# rev-tank-preamp.net
KiCad netlist of a schematic drawn in EAGLE
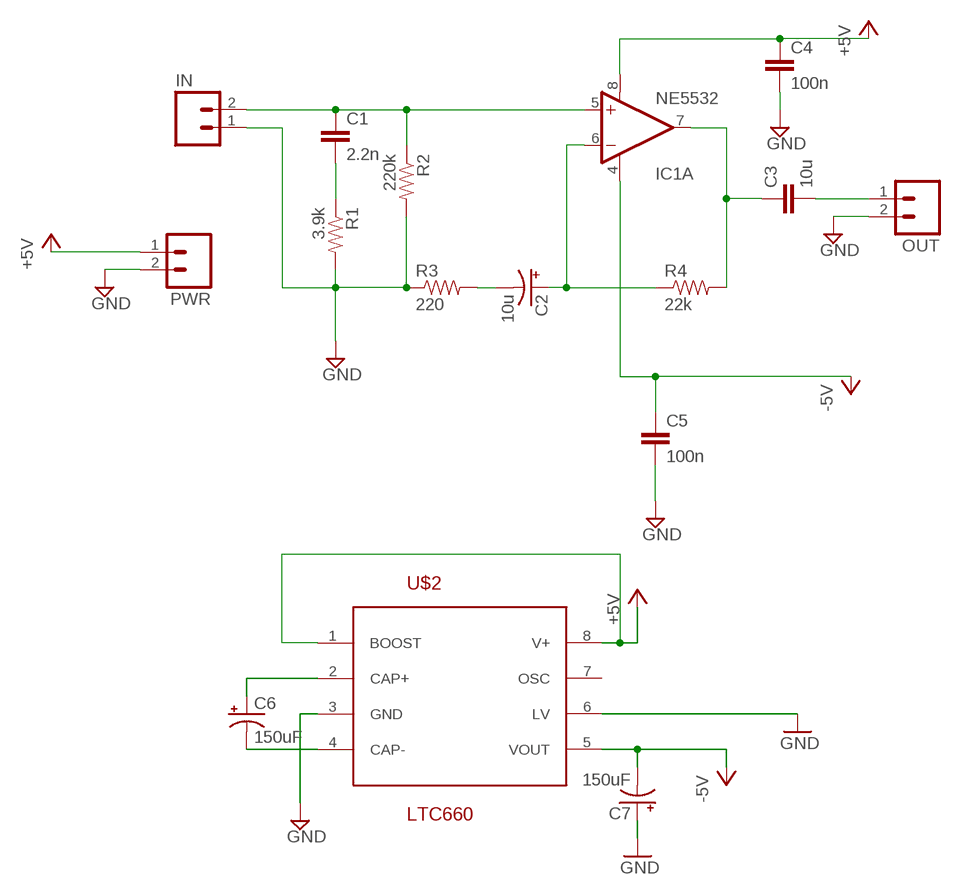
[diagram p0: schematic, sheet 1]

(export (version "E")
  (design (tool "Eeschema 10.0.6"))
  (components
    (comp (ref "C1")
      (value "2.2n")
      (footprint "eagle-import:CAP-PTH-5MM")
      (libsource (lib "eagle-import") (part "CAPPTH1"))
    )
    (comp (ref "C2")
      (value "10u")
      (footprint "eagle-import:CPOL-RADIAL-10UF-25V")
      (libsource (lib "eagle-import") (part "CAP_POLPTH2"))
    )
    (comp (ref "C3")
      (value "10u")
      (footprint "eagle-import:CAP-PTH-5MM")
      (libsource (lib "eagle-import") (part "CAPPTH1"))
    )
    (comp (ref "C4")
      (value "100n")
      (footprint "eagle-import:CAP-PTH-5MM")
      (libsource (lib "eagle-import") (part "CAPPTH1"))
    )
    (comp (ref "C5")
      (value "100n")
      (footprint "eagle-import:CAP-PTH-5MM")
      (libsource (lib "eagle-import") (part "CAPPTH1"))
    )
    (comp (ref "C6")
      (value "150uF")
      (footprint "eagle-import:CPOL-RADIAL-100UF-25V")
      (libsource (lib "eagle-import") (part "CAP_POLPTH1"))
    )
    (comp (ref "C7")
      (value "150uF")
      (footprint "eagle-import:CPOL-RADIAL-100UF-25V")
      (libsource (lib "eagle-import") (part "CAP_POLPTH1"))
    )
    (comp (ref "IC1")
      (value "NE5532")
      (footprint "eagle-import:DIP08")
      (libsource (lib "eagle-import") (part "OPAMP-DUALDIP"))
    )
    (comp (ref "IN")
      (value "M02PTH")
      (footprint "eagle-import:1X02")
      (libsource (lib "eagle-import") (part "M02PTH"))
    )
    (comp (ref "OUT")
      (value "M02PTH")
      (footprint "eagle-import:1X02")
      (libsource (lib "eagle-import") (part "M02PTH"))
    )
    (comp (ref "PWR")
      (value "M02PTH")
      (footprint "eagle-import:1X02")
      (libsource (lib "eagle-import") (part "M02PTH"))
    )
    (comp (ref "R1")
      (value "3.9k")
      (footprint "eagle-import:1_6W-RES")
      (libsource (lib "eagle-import") (part "RESISTORPTH-1/6W"))
    )
    (comp (ref "R2")
      (value "220k")
      (footprint "eagle-import:1_6W-RES")
      (libsource (lib "eagle-import") (part "RESISTORPTH-1/6W"))
    )
    (comp (ref "R3")
      (value "220")
      (footprint "eagle-import:1_6W-RES")
      (libsource (lib "eagle-import") (part "RESISTORPTH-1/6W"))
    )
    (comp (ref "R4")
      (value "22k")
      (footprint "eagle-import:1_6W-RES")
      (libsource (lib "eagle-import") (part "RESISTORPTH-1/6W"))
    )
    (comp (ref "U$2")
      (value "LTC660")
      (footprint "eagle-import:SO08")
      (libsource (lib "eagle-import") (part "LTC660"))
    )
  )
  (nets
    (net (code "1") (name "+5V") (class "Default")
      (node (ref "C4") (pin "1") (pinfunction "1_1") (pintype "passive"))
      (node (ref "IC1") (pin "8") (pinfunction "V+_8") (pintype "power_in"))
      (node (ref "PWR") (pin "1") (pinfunction "1_1") (pintype "passive"))
      (node (ref "U$2") (pin "1") (pinfunction "BOOST_1") (pintype "bidirectional"))
      (node (ref "U$2") (pin "8") (pinfunction "V+_8") (pintype "bidirectional"))
    )
    (net (code "2") (name "-5V") (class "Default")
      (node (ref "C5") (pin "1") (pinfunction "1_1") (pintype "passive"))
      (node (ref "C7") (pin "2") (pinfunction "-_2") (pintype "passive"))
      (node (ref "IC1") (pin "4") (pinfunction "V-_4") (pintype "power_in"))
      (node (ref "U$2") (pin "5") (pinfunction "VOUT_5") (pintype "bidirectional"))
    )
    (net (code "3") (name "GND") (class "Default")
      (node (ref "C4") (pin "2") (pinfunction "2_2") (pintype "passive"))
      (node (ref "C5") (pin "2") (pinfunction "2_2") (pintype "passive"))
      (node (ref "C7") (pin "1") (pinfunction "+_1") (pintype "passive"))
      (node (ref "IN") (pin "1") (pinfunction "1_1") (pintype "passive"))
      (node (ref "OUT") (pin "2") (pinfunction "2_2") (pintype "passive"))
      (node (ref "PWR") (pin "2") (pinfunction "2_2") (pintype "passive"))
      (node (ref "R1") (pin "2") (pinfunction "2_2") (pintype "passive"))
      (node (ref "R2") (pin "2") (pinfunction "2_2") (pintype "passive"))
      (node (ref "R3") (pin "1") (pinfunction "1_1") (pintype "passive"))
      (node (ref "U$2") (pin "3") (pinfunction "GND_3") (pintype "bidirectional"))
      (node (ref "U$2") (pin "6") (pinfunction "LV_6") (pintype "bidirectional"))
    )
    (net (code "4") (name "Net-(C1-Pad2)") (class "Default")
      (node (ref "C1") (pin "2") (pinfunction "2_2") (pintype "passive"))
      (node (ref "R1") (pin "1") (pinfunction "1_1") (pintype "passive"))
    )
    (net (code "5") (name "Net-(C2-+)") (class "Default")
      (node (ref "C2") (pin "1") (pinfunction "+_1") (pintype "passive"))
      (node (ref "IC1") (pin "6") (pinfunction "-IN_6") (pintype "input"))
      (node (ref "R4") (pin "1") (pinfunction "1_1") (pintype "passive"))
    )
    (net (code "6") (name "Net-(C2--)") (class "Default")
      (node (ref "C2") (pin "2") (pinfunction "-_2") (pintype "passive"))
      (node (ref "R3") (pin "2") (pinfunction "2_2") (pintype "passive"))
    )
    (net (code "7") (name "Net-(C3-Pad2)") (class "Default")
      (node (ref "C3") (pin "2") (pinfunction "2_2") (pintype "passive"))
      (node (ref "OUT") (pin "1") (pinfunction "1_1") (pintype "passive"))
    )
    (net (code "8") (name "Net-(C6-+)") (class "Default")
      (node (ref "C6") (pin "1") (pinfunction "+_1") (pintype "passive"))
      (node (ref "U$2") (pin "2") (pinfunction "CAP+_2") (pintype "bidirectional"))
    )
    (net (code "9") (name "Net-(C6--)") (class "Default")
      (node (ref "C6") (pin "2") (pinfunction "-_2") (pintype "passive"))
      (node (ref "U$2") (pin "4") (pinfunction "CAP-_4") (pintype "bidirectional"))
    )
    (net (code "10") (name "Net-(IC1A-+IN)") (class "Default")
      (node (ref "C1") (pin "1") (pinfunction "1_1") (pintype "passive"))
      (node (ref "IC1") (pin "5") (pinfunction "+IN_5") (pintype "input"))
      (node (ref "IN") (pin "2") (pinfunction "2_2") (pintype "passive"))
      (node (ref "R2") (pin "1") (pinfunction "1_1") (pintype "passive"))
    )
    (net (code "11") (name "Net-(IC1A-OUT)") (class "Default")
      (node (ref "C3") (pin "1") (pinfunction "1_1") (pintype "passive"))
      (node (ref "IC1") (pin "7") (pinfunction "OUT_7") (pintype "output"))
      (node (ref "R4") (pin "2") (pinfunction "2_2") (pintype "passive"))
    )
    (net (code "12") (name "unconnected-(U$2-OSC-Pad7)") (class "Default")
      (node (ref "U$2") (pin "7") (pinfunction "OSC_7") (pintype "bidirectional"))
    )
  )
)
